# gprs_i2c.net
KiCad netlist of a schematic drawn in EAGLE
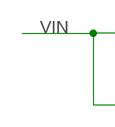
[diagram p0: schematic, sheet 1, part 1 of 2]
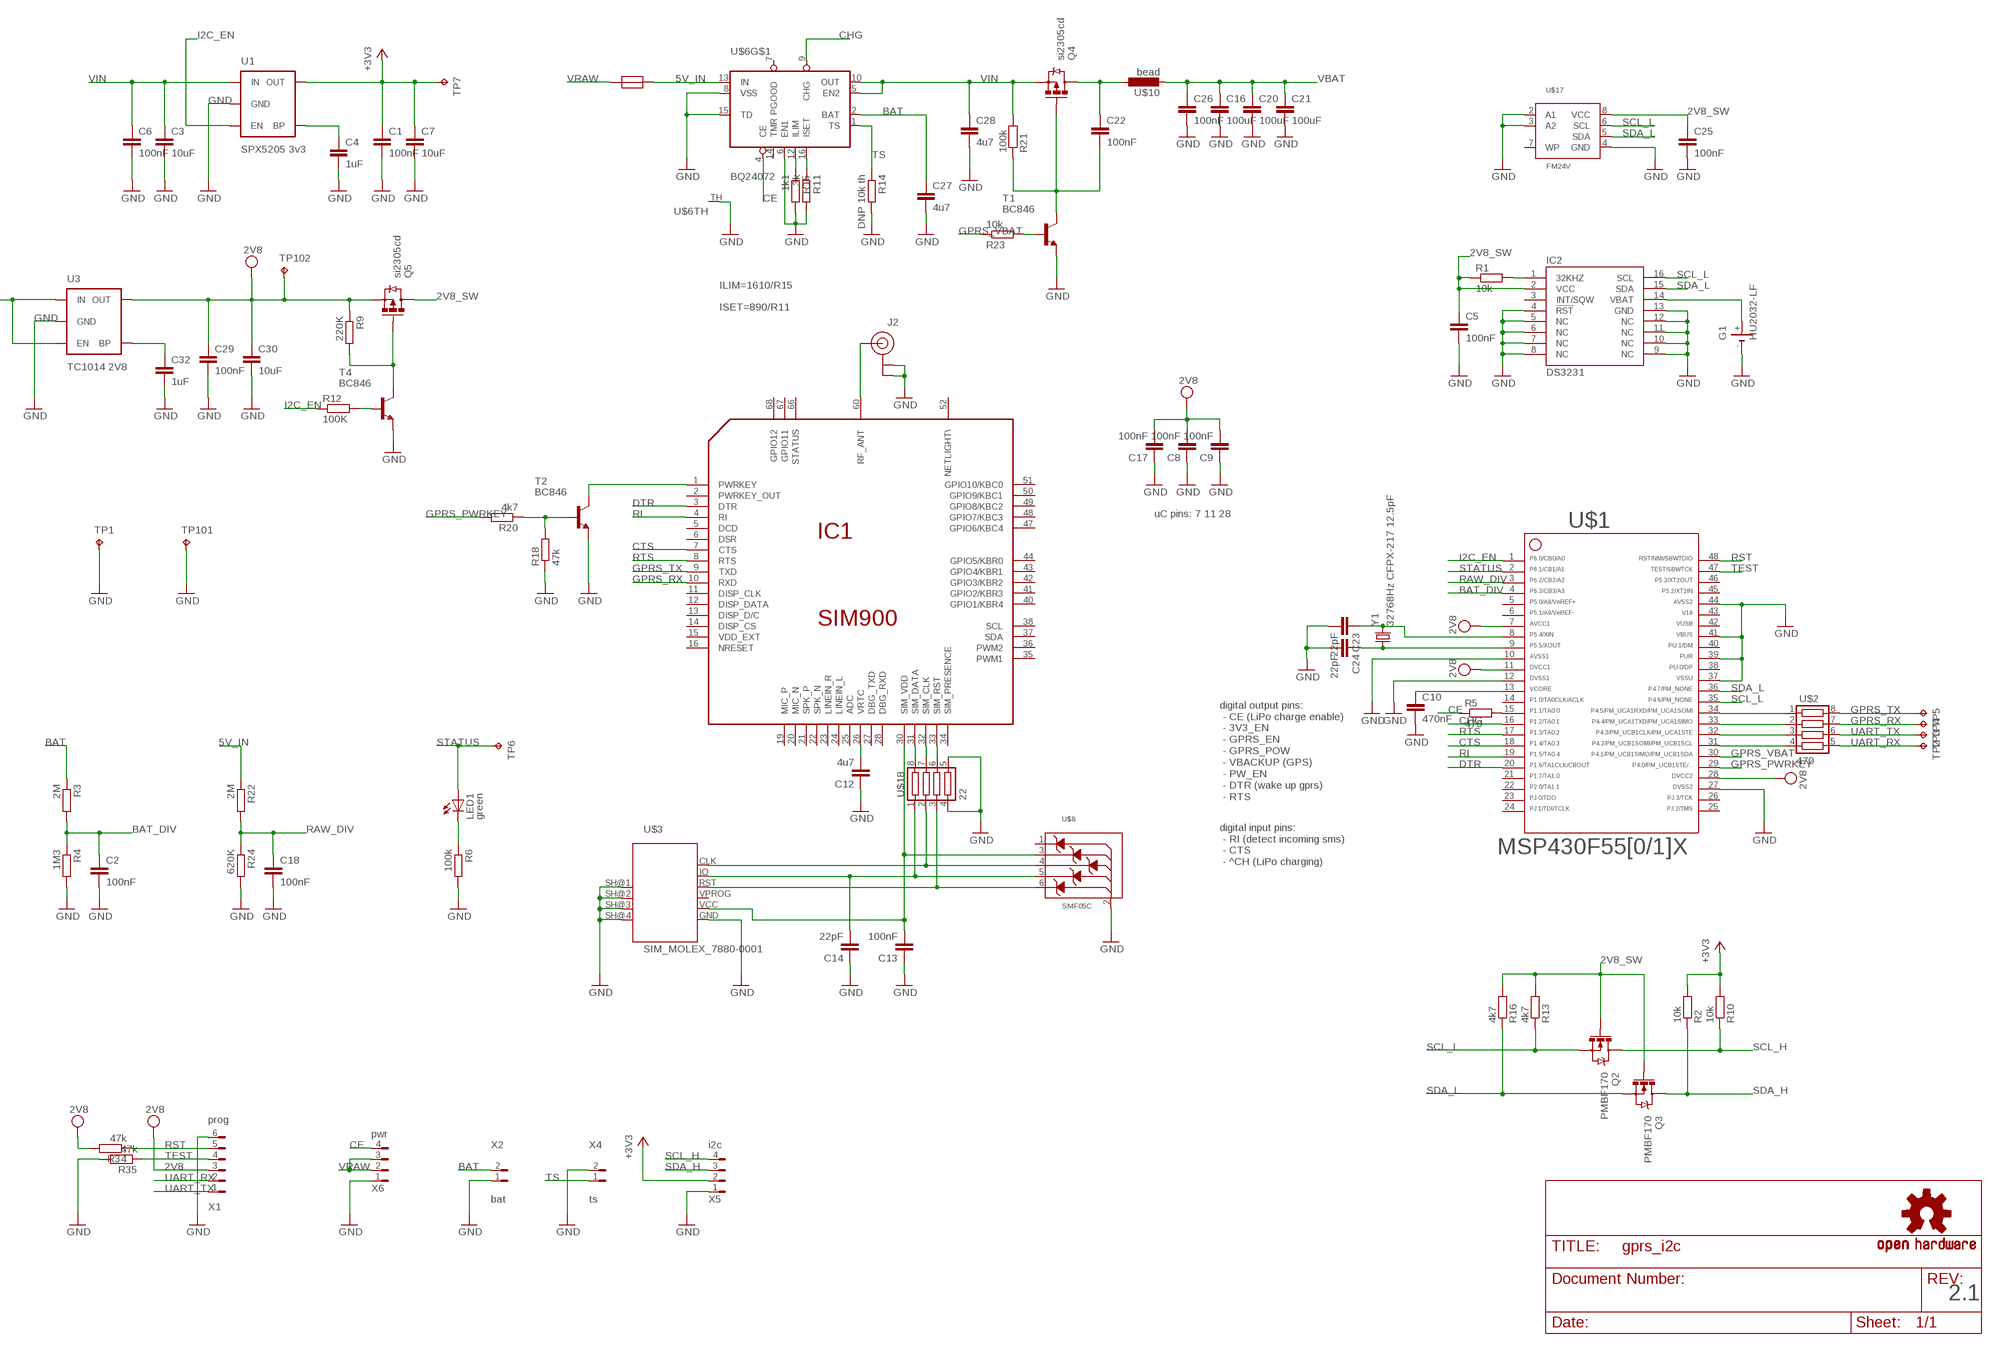
[diagram p1: schematic, sheet 1, part 2 of 2]

(export (version "E")
  (design (tool "Eeschema 10.0.6"))
  (components
    (comp (ref "C1")
      (value "100nF")
      (footprint "eagle-import:C0805")
      (libsource (lib "eagle-import") (part "C-EUC0805"))
    )
    (comp (ref "C2")
      (value "100nF")
      (footprint "eagle-import:C0805")
      (libsource (lib "eagle-import") (part "C-EUC0805"))
    )
    (comp (ref "C3")
      (value "10uF")
      (footprint "eagle-import:C0805")
      (libsource (lib "eagle-import") (part "C-EUC0805"))
    )
    (comp (ref "C4")
      (value "1uF")
      (footprint "eagle-import:C0805")
      (libsource (lib "eagle-import") (part "C-EUC0805"))
    )
    (comp (ref "C5")
      (value "100nF")
      (footprint "eagle-import:C0805")
      (libsource (lib "eagle-import") (part "C-EUC0805"))
    )
    (comp (ref "C6")
      (value "100nF")
      (footprint "eagle-import:C0805")
      (libsource (lib "eagle-import") (part "C-EUC0805"))
    )
    (comp (ref "C7")
      (value "10uF")
      (footprint "eagle-import:C1206")
      (libsource (lib "eagle-import") (part "C-EUC1206"))
    )
    (comp (ref "C8")
      (value "100nF")
      (footprint "eagle-import:C0805")
      (libsource (lib "eagle-import") (part "C-EUC0805"))
    )
    (comp (ref "C9")
      (value "100nF")
      (footprint "eagle-import:C0805")
      (libsource (lib "eagle-import") (part "C-EUC0805"))
    )
    (comp (ref "C10")
      (value "470nF")
      (footprint "eagle-import:C0805")
      (libsource (lib "eagle-import") (part "C-EUC0805"))
    )
    (comp (ref "C12")
      (value "4u7")
      (footprint "eagle-import:C0805")
      (libsource (lib "eagle-import") (part "C-EUC0805"))
    )
    (comp (ref "C13")
      (value "100nF")
      (footprint "eagle-import:C0805")
      (libsource (lib "eagle-import") (part "C-EUC0805"))
    )
    (comp (ref "C14")
      (value "22pF")
      (footprint "eagle-import:C0805")
      (libsource (lib "eagle-import") (part "C-EUC0805"))
    )
    (comp (ref "C16")
      (value "100uF")
      (footprint "eagle-import:C1206")
      (libsource (lib "eagle-import") (part "C-EUC1206"))
    )
    (comp (ref "C17")
      (value "100nF")
      (footprint "eagle-import:C0805")
      (libsource (lib "eagle-import") (part "C-EUC0805"))
    )
    (comp (ref "C18")
      (value "100nF")
      (footprint "eagle-import:C0805")
      (libsource (lib "eagle-import") (part "C-EUC0805"))
    )
    (comp (ref "C20")
      (value "100uF")
      (footprint "eagle-import:C1206")
      (libsource (lib "eagle-import") (part "C-EUC1206"))
    )
    (comp (ref "C21")
      (value "100uF")
      (footprint "eagle-import:C1206")
      (libsource (lib "eagle-import") (part "C-EUC1206"))
    )
    (comp (ref "C22")
      (value "100nF")
      (footprint "eagle-import:C0805")
      (libsource (lib "eagle-import") (part "C-EUC0805"))
    )
    (comp (ref "C23")
      (value "22pF")
      (footprint "eagle-import:C0805")
      (libsource (lib "eagle-import") (part "C-EUC0805"))
    )
    (comp (ref "C24")
      (value "22pF")
      (footprint "eagle-import:C0805")
      (libsource (lib "eagle-import") (part "C-EUC0805"))
    )
    (comp (ref "C25")
      (value "100nF")
      (footprint "eagle-import:C0805")
      (libsource (lib "eagle-import") (part "C-EUC0805"))
    )
    (comp (ref "C26")
      (value "100nF")
      (footprint "eagle-import:C0805")
      (libsource (lib "eagle-import") (part "C-EUC0805"))
    )
    (comp (ref "C27")
      (value "4u7")
      (footprint "eagle-import:C1206")
      (libsource (lib "eagle-import") (part "C-EUC1206"))
    )
    (comp (ref "C28")
      (value "4u7")
      (footprint "eagle-import:C1206")
      (libsource (lib "eagle-import") (part "C-EUC1206"))
    )
    (comp (ref "C29")
      (value "100nF")
      (footprint "eagle-import:C0805")
      (libsource (lib "eagle-import") (part "C-EUC0805"))
    )
    (comp (ref "C30")
      (value "10uF")
      (footprint "eagle-import:C1206")
      (libsource (lib "eagle-import") (part "C-EUC1206"))
    )
    (comp (ref "C32")
      (value "1uF")
      (footprint "eagle-import:C0805")
      (libsource (lib "eagle-import") (part "C-EUC0805"))
    )
    (comp (ref "G1")
      (value "HU2032-LF")
      (footprint "eagle-import:HU2032-LF")
      (libsource (lib "eagle-import") (part "HU2032-LF"))
    )
    (comp (ref "IC1")
      (value "SIM900")
      (footprint "eagle-import:SIM900")
      (libsource (lib "eagle-import") (part "SIM900"))
    )
    (comp (ref "IC2")
      (value "DS3231")
      (footprint "eagle-import:SO-16")
      (libsource (lib "eagle-import") (part "DS3231"))
    )
    (comp (ref "J2")
      (value "U.FL")
      (footprint "eagle-import:U.FL")
      (libsource (lib "eagle-import") (part "U.FL"))
    )
    (comp (ref "LED1")
      (value "green")
      (footprint "eagle-import:CHIPLED_0805")
      (libsource (lib "eagle-import") (part "LEDCHIPLED_0805"))
    )
    (comp (ref "Q2")
      (value "PMBF170")
      (footprint "eagle-import:SOT23-3")
      (libsource (lib "eagle-import") (part "MOSFET-NCHANNEL_SOT23-3"))
    )
    (comp (ref "Q3")
      (value "PMBF170")
      (footprint "eagle-import:SOT23-3")
      (libsource (lib "eagle-import") (part "MOSFET-NCHANNEL_SOT23-3"))
    )
    (comp (ref "Q4")
      (value "si2305cd")
      (footprint "eagle-import:SOT23-3_POWER@1")
      (libsource (lib "eagle-import") (part "MOSFET-PCHANNELSMD_POWER"))
    )
    (comp (ref "Q5")
      (value "si2305cd")
      (footprint "eagle-import:SOT23-3_POWER@1")
      (libsource (lib "eagle-import") (part "MOSFET-PCHANNELSMD_POWER"))
    )
    (comp (ref "R1")
      (value "10k")
      (footprint "eagle-import:R0805W")
      (libsource (lib "eagle-import") (part "R-EU_R0805W"))
    )
    (comp (ref "R2")
      (value "10k")
      (footprint "eagle-import:R0805W")
      (libsource (lib "eagle-import") (part "R-EU_R0805W"))
    )
    (comp (ref "R3")
      (value "2M")
      (footprint "eagle-import:R0805W")
      (libsource (lib "eagle-import") (part "R-EU_R0805W"))
    )
    (comp (ref "R4")
      (value "1M3")
      (footprint "eagle-import:R0805W")
      (libsource (lib "eagle-import") (part "R-EU_R0805W"))
    )
    (comp (ref "R5")
      (value "470")
      (footprint "eagle-import:R0805W")
      (libsource (lib "eagle-import") (part "R-EU_R0805W"))
    )
    (comp (ref "R6")
      (value "100k")
      (footprint "eagle-import:R0805W")
      (libsource (lib "eagle-import") (part "R-EU_R0805W"))
    )
    (comp (ref "R9")
      (value "220K")
      (footprint "eagle-import:R0805W")
      (libsource (lib "eagle-import") (part "R-EU_R0805W"))
    )
    (comp (ref "R10")
      (value "10k")
      (footprint "eagle-import:R0805W")
      (libsource (lib "eagle-import") (part "R-EU_R0805W"))
    )
    (comp (ref "R11")
      (value "3k")
      (footprint "eagle-import:R0805W")
      (libsource (lib "eagle-import") (part "R-EU_R0805W"))
    )
    (comp (ref "R12")
      (value "100K")
      (footprint "eagle-import:R0805W")
      (libsource (lib "eagle-import") (part "R-EU_R0805W"))
    )
    (comp (ref "R13")
      (value "4k7")
      (footprint "eagle-import:R0805W")
      (libsource (lib "eagle-import") (part "R-EU_R0805W"))
    )
    (comp (ref "R14")
      (value "DNP 10k th")
      (footprint "eagle-import:R0805W")
      (libsource (lib "eagle-import") (part "R-EU_R0805W"))
    )
    (comp (ref "R15")
      (value "1k1")
      (footprint "eagle-import:R0805W")
      (libsource (lib "eagle-import") (part "R-EU_R0805W"))
    )
    (comp (ref "R16")
      (value "4k7")
      (footprint "eagle-import:R0805W")
      (libsource (lib "eagle-import") (part "R-EU_R0805W"))
    )
    (comp (ref "R18")
      (value "47k")
      (footprint "eagle-import:R0805W")
      (libsource (lib "eagle-import") (part "R-EU_R0805W"))
    )
    (comp (ref "R20")
      (value "4k7")
      (footprint "eagle-import:R0805W")
      (libsource (lib "eagle-import") (part "R-EU_R0805W"))
    )
    (comp (ref "R21")
      (value "100k")
      (footprint "eagle-import:R0805W")
      (libsource (lib "eagle-import") (part "R-EU_R0805W"))
    )
    (comp (ref "R22")
      (value "2M")
      (footprint "eagle-import:R0805W")
      (libsource (lib "eagle-import") (part "R-EU_R0805W"))
    )
    (comp (ref "R23")
      (value "10k")
      (footprint "eagle-import:R0805W")
      (libsource (lib "eagle-import") (part "R-EU_R0805W"))
    )
    (comp (ref "R24")
      (value "620K")
      (footprint "eagle-import:R0805W")
      (libsource (lib "eagle-import") (part "R-EU_R0805W"))
    )
    (comp (ref "R34")
      (value "47k")
      (footprint "eagle-import:R0805W")
      (libsource (lib "eagle-import") (part "R-EU_R0805W"))
    )
    (comp (ref "R35")
      (value "47k")
      (footprint "eagle-import:R0805W")
      (libsource (lib "eagle-import") (part "R-EU_R0805W"))
    )
    (comp (ref "T1")
      (value "BC846")
      (footprint "eagle-import:SOT23")
      (libsource (lib "eagle-import") (part "BC846"))
    )
    (comp (ref "T2")
      (value "BC846")
      (footprint "eagle-import:SOT23")
      (libsource (lib "eagle-import") (part "BC846"))
    )
    (comp (ref "T4")
      (value "BC846")
      (footprint "eagle-import:SOT23")
      (libsource (lib "eagle-import") (part "BC846"))
    )
    (comp (ref "TP1")
      (value "TPTP12R")
      (footprint "eagle-import:TP12R")
      (libsource (lib "eagle-import") (part "TPTP12R"))
    )
    (comp (ref "TP2")
      (value "TPTP12R")
      (footprint "eagle-import:TP12R")
      (libsource (lib "eagle-import") (part "TPTP12R"))
    )
    (comp (ref "TP3")
      (value "TPTP12R")
      (footprint "eagle-import:TP12R")
      (libsource (lib "eagle-import") (part "TPTP12R"))
    )
    (comp (ref "TP4")
      (value "TPTP12R")
      (footprint "eagle-import:TP12R")
      (libsource (lib "eagle-import") (part "TPTP12R"))
    )
    (comp (ref "TP5")
      (value "TPTP12R")
      (footprint "eagle-import:TP12R")
      (libsource (lib "eagle-import") (part "TPTP12R"))
    )
    (comp (ref "TP6")
      (value "TPTP12R")
      (footprint "eagle-import:TP12R")
      (libsource (lib "eagle-import") (part "TPTP12R"))
    )
    (comp (ref "TP7")
      (value "TPTP12R")
      (footprint "eagle-import:TP12R")
      (libsource (lib "eagle-import") (part "TPTP12R"))
    )
    (comp (ref "TP101")
      (value "TPTP12R")
      (footprint "eagle-import:TP12R")
      (libsource (lib "eagle-import") (part "TPTP12R"))
    )
    (comp (ref "TP102")
      (value "TPTP12R")
      (footprint "eagle-import:TP12R")
      (libsource (lib "eagle-import") (part "TPTP12R"))
    )
    (comp (ref "U$1")
      (value "MSP430F5510")
      (footprint "eagle-import:PT48")
      (libsource (lib "eagle-import") (part "F55[0/1]X---PT48"))
    )
    (comp (ref "U$2")
      (value "470")
      (footprint "eagle-import:YC164")
      (libsource (lib "eagle-import") (part "RES_ARR"))
    )
    (comp (ref "U$3")
      (value "SIM_MOLEX_7880-0001")
      (footprint "eagle-import:MOLEX_7880-0001")
      (libsource (lib "eagle-import") (part "SIM_MOLEX_7880-0001"))
    )
    (comp (ref "U$5")
      (value "RESETTABLE_0805")
      (footprint "eagle-import:0805W")
      (libsource (lib "eagle-import") (part "RESETTABLE_0805"))
    )
    (comp (ref "U$6")
      (value "BQ24072")
      (footprint "eagle-import:S-PVQFN-N16")
      (libsource (lib "eagle-import") (part "BQ24072"))
    )
    (comp (ref "U$7")
      (value "OSHW-LOGOM")
      (footprint "eagle-import:OSHW-LOGO-M")
      (libsource (lib "eagle-import") (part "OSHW-LOGOM"))
    )
    (comp (ref "U$8")
      (value "SMF05C")
      (footprint "eagle-import:SC-88")
      (libsource (lib "eagle-import") (part "SMF05C"))
    )
    (comp (ref "U$10")
      (value "bead")
      (footprint "eagle-import:L0805W")
      (libsource (lib "eagle-import") (part "INDUCTOR"))
    )
    (comp (ref "U$17")
      (value "FM24V")
      (footprint "eagle-import:SO-08")
      (libsource (lib "eagle-import") (part "FM24V"))
    )
    (comp (ref "U$18")
      (value "22")
      (footprint "eagle-import:YC164")
      (libsource (lib "eagle-import") (part "RES_ARR"))
    )
    (comp (ref "U1")
      (value "SPX5205 3v3")
      (footprint "eagle-import:SOT23-5")
      (libsource (lib "eagle-import") (part "V_REG_LDOSMD"))
    )
    (comp (ref "U3")
      (value "TC1014 2V8")
      (footprint "eagle-import:SOT23-5")
      (libsource (lib "eagle-import") (part "V_REG_LDOSMD"))
    )
    (comp (ref "X1")
      (value "prog")
      (footprint "eagle-import:0530470610")
      (libsource (lib "eagle-import") (part "MOLEX_6VERTICAL"))
    )
    (comp (ref "X2")
      (value "bat")
      (footprint "eagle-import:0530480210")
      (libsource (lib "eagle-import") (part "MOLEX_2HORIZONTAL"))
    )
    (comp (ref "X4")
      (value "ts")
      (footprint "eagle-import:0530480210")
      (libsource (lib "eagle-import") (part "MOLEX_2HORIZONTAL"))
    )
    (comp (ref "X5")
      (value "i2c")
      (footprint "eagle-import:0530480401")
      (libsource (lib "eagle-import") (part "MOLEX_4HORIZONTAL"))
    )
    (comp (ref "X6")
      (value "pwr")
      (footprint "eagle-import:0530480401")
      (libsource (lib "eagle-import") (part "MOLEX_4HORIZONTAL"))
    )
    (comp (ref "Y1")
      (value "32768Hz CFPX-217 12.5pF")
      (footprint "eagle-import:CRYSTAL-SMD-3.2X1.5")
      (libsource (lib "eagle-import") (part "CRYSTAL3.2X1.5"))
    )
  )
  (nets
    (net (code "1") (name "+3V3") (class "Default")
      (node (ref "C1") (pin "1") (pinfunction "1_1") (pintype "passive"))
      (node (ref "C7") (pin "1") (pinfunction "1_1") (pintype "passive"))
      (node (ref "R10") (pin "2") (pinfunction "2_2") (pintype "passive"))
      (node (ref "R2") (pin "2") (pinfunction "2_2") (pintype "passive"))
      (node (ref "TP7") (pin "TP") (pinfunction "TP_TP") (pintype "input"))
      (node (ref "U1") (pin "5") (pinfunction "OUT_5") (pintype "passive"))
      (node (ref "X5") (pin "2") (pinfunction "3_2") (pintype "passive"))
    )
    (net (code "2") (name "/2V8_SW") (class "Default")
      (node (ref "C25") (pin "1") (pinfunction "1_1") (pintype "passive"))
      (node (ref "C5") (pin "1") (pinfunction "1_1") (pintype "passive"))
      (node (ref "IC2") (pin "2") (pinfunction "VCC_2") (pintype "power_in"))
      (node (ref "Q2") (pin "1") (pinfunction "G_1") (pintype "passive"))
      (node (ref "Q3") (pin "1") (pinfunction "G_1") (pintype "passive"))
      (node (ref "Q5") (pin "3") (pinfunction "D_3") (pintype "passive"))
      (node (ref "R1") (pin "1") (pinfunction "1_1") (pintype "passive"))
      (node (ref "R13") (pin "2") (pinfunction "2_2") (pintype "passive"))
      (node (ref "R16") (pin "2") (pinfunction "2_2") (pintype "passive"))
      (node (ref "U$17") (pin "8") (pinfunction "VCC_8") (pintype "bidirectional"))
    )
    (net (code "3") (name "/5V_IN") (class "Default")
      (node (ref "R22") (pin "1") (pinfunction "1_1") (pintype "passive"))
      (node (ref "U$5") (pin "2") (pinfunction "P$2_2") (pintype "bidirectional"))
      (node (ref "U$6") (pin "13") (pinfunction "IN_13") (pintype "input"))
    )
    (net (code "4") (name "/42") (class "Default")
      (node (ref "U$1") (pin "42") (pinfunction "42_42") (pintype "power_in"))
    )
    (net (code "5") (name "/43") (class "Default")
      (node (ref "U$1") (pin "43") (pinfunction "43_43") (pintype "power_in"))
    )
    (net (code "6") (name "/46") (class "Default")
      (node (ref "U$1") (pin "46") (pinfunction "46_46") (pintype "power_in"))
    )
    (net (code "7") (name "/BAT") (class "Default")
      (node (ref "C27") (pin "1") (pinfunction "1_1") (pintype "passive"))
      (node (ref "R3") (pin "1") (pinfunction "1_1") (pintype "passive"))
      (node (ref "U$6") (pin "2") (pinfunction "BAT_2") (pintype "input"))
      (node (ref "X2") (pin "2") (pinfunction "1_2") (pintype "passive"))
    )
    (net (code "8") (name "/BAT_DIV") (class "Default")
      (node (ref "C2") (pin "1") (pinfunction "1_1") (pintype "passive"))
      (node (ref "R3") (pin "2") (pinfunction "2_2") (pintype "passive"))
      (node (ref "R4") (pin "1") (pinfunction "1_1") (pintype "passive"))
      (node (ref "U$1") (pin "4") (pinfunction "4_4") (pintype "bidirectional"))
    )
    (net (code "9") (name "/CE") (class "Default")
      (node (ref "R5") (pin "1") (pinfunction "1_1") (pintype "passive"))
      (node (ref "U$6") (pin "4") (pinfunction "CE_4") (pintype "bidirectional"))
      (node (ref "X6") (pin "4") (pinfunction "1_4") (pintype "passive"))
    )
    (net (code "10") (name "/CHG") (class "Default")
      (node (ref "U$1") (pin "16") (pinfunction "16_16") (pintype "bidirectional"))
      (node (ref "U$6") (pin "9") (pinfunction "CHG_9") (pintype "bidirectional"))
    )
    (net (code "11") (name "/CTS") (class "Default")
      (node (ref "IC1") (pin "7") (pinfunction "CTS_7") (pintype "bidirectional"))
      (node (ref "U$1") (pin "18") (pinfunction "18_18") (pintype "bidirectional"))
    )
    (net (code "12") (name "/DTR") (class "Default")
      (node (ref "IC1") (pin "3") (pinfunction "DTR_3") (pintype "bidirectional"))
      (node (ref "U$1") (pin "20") (pinfunction "20_20") (pintype "bidirectional"))
    )
    (net (code "13") (name "/GPRS_PWRKEY") (class "Default")
      (node (ref "R20") (pin "2") (pinfunction "2_2") (pintype "passive"))
      (node (ref "U$1") (pin "29") (pinfunction "29_29") (pintype "bidirectional"))
    )
    (net (code "14") (name "/GPRS_RX") (class "Default")
      (node (ref "IC1") (pin "10") (pinfunction "RXD_10") (pintype "bidirectional"))
      (node (ref "TP4") (pin "TP") (pinfunction "TP_TP") (pintype "input"))
      (node (ref "U$2") (pin "7") (pinfunction "7_7") (pintype "passive"))
    )
    (net (code "15") (name "/GPRS_TX") (class "Default")
      (node (ref "IC1") (pin "9") (pinfunction "TXD_9") (pintype "bidirectional"))
      (node (ref "TP5") (pin "TP") (pinfunction "TP_TP") (pintype "input"))
      (node (ref "U$2") (pin "8") (pinfunction "8_8") (pintype "passive"))
    )
    (net (code "16") (name "/GPRS_VBAT") (class "Default")
      (node (ref "R23") (pin "1") (pinfunction "1_1") (pintype "passive"))
      (node (ref "U$1") (pin "30") (pinfunction "30_30") (pintype "bidirectional"))
    )
    (net (code "17") (name "/I2C_EN") (class "Default")
      (node (ref "R12") (pin "1") (pinfunction "1_1") (pintype "passive"))
      (node (ref "U$1") (pin "1") (pinfunction "1_1") (pintype "bidirectional"))
      (node (ref "U1") (pin "3") (pinfunction "EN_3") (pintype "input"))
    )
    (net (code "18") (name "/RAW_DIV") (class "Default")
      (node (ref "C18") (pin "1") (pinfunction "1_1") (pintype "passive"))
      (node (ref "R22") (pin "2") (pinfunction "2_2") (pintype "passive"))
      (node (ref "R24") (pin "1") (pinfunction "1_1") (pintype "passive"))
      (node (ref "U$1") (pin "3") (pinfunction "3_3") (pintype "bidirectional"))
    )
    (net (code "19") (name "/RI") (class "Default")
      (node (ref "IC1") (pin "4") (pinfunction "RI_4") (pintype "bidirectional"))
      (node (ref "U$1") (pin "19") (pinfunction "19_19") (pintype "bidirectional"))
    )
    (net (code "20") (name "/RST") (class "Default")
      (node (ref "R34") (pin "1") (pinfunction "1_1") (pintype "passive"))
      (node (ref "U$1") (pin "48") (pinfunction "48_48") (pintype "bidirectional"))
      (node (ref "X1") (pin "5") (pinfunction "5_5") (pintype "passive"))
    )
    (net (code "21") (name "/RTS") (class "Default")
      (node (ref "IC1") (pin "8") (pinfunction "RTS_8") (pintype "bidirectional"))
      (node (ref "U$1") (pin "17") (pinfunction "17_17") (pintype "bidirectional"))
    )
    (net (code "22") (name "/SCL_H") (class "Default")
      (node (ref "Q2") (pin "3") (pinfunction "D_3") (pintype "passive"))
      (node (ref "R10") (pin "1") (pinfunction "1_1") (pintype "passive"))
      (node (ref "X5") (pin "4") (pinfunction "1_4") (pintype "passive"))
    )
    (net (code "23") (name "/SCL_L") (class "Default")
      (node (ref "IC2") (pin "16") (pinfunction "SCL_16") (pintype "bidirectional"))
      (node (ref "Q2") (pin "2") (pinfunction "S_2") (pintype "passive"))
      (node (ref "R13") (pin "1") (pinfunction "1_1") (pintype "passive"))
      (node (ref "U$1") (pin "35") (pinfunction "35_35") (pintype "bidirectional"))
      (node (ref "U$17") (pin "6") (pinfunction "SCL_6") (pintype "bidirectional"))
    )
    (net (code "24") (name "/SDA_H") (class "Default")
      (node (ref "Q3") (pin "3") (pinfunction "D_3") (pintype "passive"))
      (node (ref "R2") (pin "1") (pinfunction "1_1") (pintype "passive"))
      (node (ref "X5") (pin "3") (pinfunction "2_3") (pintype "passive"))
    )
    (net (code "25") (name "/SDA_L") (class "Default")
      (node (ref "IC2") (pin "15") (pinfunction "SDA_15") (pintype "bidirectional"))
      (node (ref "Q3") (pin "2") (pinfunction "S_2") (pintype "passive"))
      (node (ref "R16") (pin "1") (pinfunction "1_1") (pintype "passive"))
      (node (ref "U$1") (pin "36") (pinfunction "36_36") (pintype "bidirectional"))
      (node (ref "U$17") (pin "5") (pinfunction "SDA_5") (pintype "bidirectional"))
    )
    (net (code "26") (name "/STATUS") (class "Default")
      (node (ref "LED1") (pin "A") (pinfunction "A_A") (pintype "passive"))
      (node (ref "TP6") (pin "TP") (pinfunction "TP_TP") (pintype "input"))
      (node (ref "U$1") (pin "2") (pinfunction "2_2") (pintype "bidirectional"))
    )
    (net (code "27") (name "/TEST") (class "Default")
      (node (ref "R35") (pin "1") (pinfunction "1_1") (pintype "passive"))
      (node (ref "U$1") (pin "47") (pinfunction "47_47") (pintype "input"))
      (node (ref "X1") (pin "4") (pinfunction "4_4") (pintype "passive"))
    )
    (net (code "28") (name "/TS") (class "Default")
      (node (ref "R14") (pin "1") (pinfunction "1_1") (pintype "passive"))
      (node (ref "U$6") (pin "1") (pinfunction "TS_1") (pintype "input"))
      (node (ref "X4") (pin "1") (pinfunction "2_1") (pintype "passive"))
    )
    (net (code "29") (name "/UART_RX") (class "Default")
      (node (ref "TP2") (pin "TP") (pinfunction "TP_TP") (pintype "input"))
      (node (ref "U$2") (pin "5") (pinfunction "5_5") (pintype "passive"))
      (node (ref "X1") (pin "2") (pinfunction "2_2") (pintype "passive"))
    )
    (net (code "30") (name "/UART_TX") (class "Default")
      (node (ref "TP3") (pin "TP") (pinfunction "TP_TP") (pintype "input"))
      (node (ref "U$2") (pin "6") (pinfunction "6_6") (pintype "passive"))
      (node (ref "X1") (pin "1") (pinfunction "1_1") (pintype "passive"))
    )
    (net (code "31") (name "/VBAT") (class "Default")
      (node (ref "C16") (pin "1") (pinfunction "1_1") (pintype "passive"))
      (node (ref "C20") (pin "1") (pinfunction "1_1") (pintype "passive"))
      (node (ref "C21") (pin "1") (pinfunction "1_1") (pintype "passive"))
      (node (ref "C26") (pin "1") (pinfunction "1_1") (pintype "passive"))
      (node (ref "U$10") (pin "2") (pinfunction "2_2") (pintype "passive"))
    )
    (net (code "32") (name "/VIN") (class "Default")
      (node (ref "C28") (pin "1") (pinfunction "1_1") (pintype "passive"))
      (node (ref "C3") (pin "1") (pinfunction "1_1") (pintype "passive"))
      (node (ref "C6") (pin "1") (pinfunction "1_1") (pintype "passive"))
      (node (ref "Q4") (pin "2") (pinfunction "S_2") (pintype "passive"))
      (node (ref "R21") (pin "2") (pinfunction "2_2") (pintype "passive"))
      (node (ref "U$6") (pin "10") (pinfunction "OUT_10") (pintype "output"))
      (node (ref "U$6") (pin "5") (pinfunction "EN2_5") (pintype "input"))
      (node (ref "U1") (pin "1") (pinfunction "IN_1") (pintype "input"))
      (node (ref "U3") (pin "1") (pinfunction "IN_1") (pintype "input"))
      (node (ref "U3") (pin "3") (pinfunction "EN_3") (pintype "input"))
    )
    (net (code "33") (name "/VRAW") (class "Default")
      (node (ref "U$5") (pin "1") (pinfunction "P$1_1") (pintype "bidirectional"))
      (node (ref "X6") (pin "2") (pinfunction "3_2") (pintype "passive"))
      (node (ref "X6") (pin "3") (pinfunction "2_3") (pintype "passive"))
    )
    (net (code "34") (name "2V8") (class "Default")
      (node (ref "C17") (pin "2") (pinfunction "2_2") (pintype "passive"))
      (node (ref "C29") (pin "1") (pinfunction "1_1") (pintype "passive"))
      (node (ref "C30") (pin "1") (pinfunction "1_1") (pintype "passive"))
      (node (ref "C8") (pin "2") (pinfunction "2_2") (pintype "passive"))
      (node (ref "C9") (pin "2") (pinfunction "2_2") (pintype "passive"))
      (node (ref "Q5") (pin "2") (pinfunction "S_2") (pintype "passive"))
      (node (ref "R34") (pin "2") (pinfunction "2_2") (pintype "passive"))
      (node (ref "R9") (pin "1") (pinfunction "1_1") (pintype "passive"))
      (node (ref "TP102") (pin "TP") (pinfunction "TP_TP") (pintype "input"))
      (node (ref "U$1") (pin "11") (pinfunction "11_11") (pintype "power_in"))
      (node (ref "U$1") (pin "28") (pinfunction "28_28") (pintype "power_in"))
      (node (ref "U$1") (pin "7") (pinfunction "7_7") (pintype "power_in"))
      (node (ref "U3") (pin "5") (pinfunction "OUT_5") (pintype "passive"))
      (node (ref "X1") (pin "3") (pinfunction "3_3") (pintype "passive"))
    )
    (net (code "35") (name "GND") (class "Default")
      (node (ref "C1") (pin "2") (pinfunction "2_2") (pintype "passive"))
      (node (ref "C10") (pin "2") (pinfunction "2_2") (pintype "passive"))
      (node (ref "C12") (pin "1") (pinfunction "1_1") (pintype "passive"))
      (node (ref "C13") (pin "1") (pinfunction "1_1") (pintype "passive"))
      (node (ref "C14") (pin "1") (pinfunction "1_1") (pintype "passive"))
      (node (ref "C16") (pin "2") (pinfunction "2_2") (pintype "passive"))
      (node (ref "C17") (pin "1") (pinfunction "1_1") (pintype "passive"))
      (node (ref "C18") (pin "2") (pinfunction "2_2") (pintype "passive"))
      (node (ref "C2") (pin "2") (pinfunction "2_2") (pintype "passive"))
      (node (ref "C20") (pin "2") (pinfunction "2_2") (pintype "passive"))
      (node (ref "C21") (pin "2") (pinfunction "2_2") (pintype "passive"))
      (node (ref "C23") (pin "2") (pinfunction "2_2") (pintype "passive"))
      (node (ref "C24") (pin "2") (pinfunction "2_2") (pintype "passive"))
      (node (ref "C25") (pin "2") (pinfunction "2_2") (pintype "passive"))
      (node (ref "C26") (pin "2") (pinfunction "2_2") (pintype "passive"))
      (node (ref "C27") (pin "2") (pinfunction "2_2") (pintype "passive"))
      (node (ref "C28") (pin "2") (pinfunction "2_2") (pintype "passive"))
      (node (ref "C29") (pin "2") (pinfunction "2_2") (pintype "passive"))
      (node (ref "C3") (pin "2") (pinfunction "2_2") (pintype "passive"))
      (node (ref "C30") (pin "2") (pinfunction "2_2") (pintype "passive"))
      (node (ref "C32") (pin "2") (pinfunction "2_2") (pintype "passive"))
      (node (ref "C4") (pin "2") (pinfunction "2_2") (pintype "passive"))
      (node (ref "C5") (pin "2") (pinfunction "2_2") (pintype "passive"))
      (node (ref "C6") (pin "2") (pinfunction "2_2") (pintype "passive"))
      (node (ref "C7") (pin "2") (pinfunction "2_2") (pintype "passive"))
      (node (ref "C8") (pin "1") (pinfunction "1_1") (pintype "passive"))
      (node (ref "C9") (pin "1") (pinfunction "1_1") (pintype "passive"))
      (node (ref "G1") (pin "-") (pinfunction "-_-") (pintype "passive"))
      (node (ref "IC2") (pin "10") (pinfunction "NC_10") (pintype "bidirectional"))
      (node (ref "IC2") (pin "11") (pinfunction "NC_11") (pintype "bidirectional"))
      (node (ref "IC2") (pin "12") (pinfunction "NC_12") (pintype "bidirectional"))
      (node (ref "IC2") (pin "13") (pinfunction "GND_13") (pintype "power_in"))
      (node (ref "IC2") (pin "4") (pinfunction "~{RST}_4") (pintype "bidirectional"))
      (node (ref "IC2") (pin "5") (pinfunction "NC_5") (pintype "bidirectional"))
      (node (ref "IC2") (pin "6") (pinfunction "NC_6") (pintype "bidirectional"))
      (node (ref "IC2") (pin "7") (pinfunction "NC_7") (pintype "bidirectional"))
      (node (ref "IC2") (pin "8") (pinfunction "NC_8") (pintype "bidirectional"))
      (node (ref "IC2") (pin "9") (pinfunction "NC_9") (pintype "bidirectional"))
      (node (ref "J2") (pin "P$1") (pinfunction "GND_P$1") (pintype "bidirectional"))
      (node (ref "J2") (pin "P$2") (pinfunction "GND_P$2") (pintype "bidirectional"))
      (node (ref "R11") (pin "2") (pinfunction "2_2") (pintype "passive"))
      (node (ref "R14") (pin "2") (pinfunction "2_2") (pintype "passive"))
      (node (ref "R15") (pin "2") (pinfunction "2_2") (pintype "passive"))
      (node (ref "R18") (pin "1") (pinfunction "1_1") (pintype "passive"))
      (node (ref "R24") (pin "2") (pinfunction "2_2") (pintype "passive"))
      (node (ref "R35") (pin "2") (pinfunction "2_2") (pintype "passive"))
      (node (ref "R4") (pin "2") (pinfunction "2_2") (pintype "passive"))
      (node (ref "R6") (pin "2") (pinfunction "2_2") (pintype "passive"))
      (node (ref "T1") (pin "2") (pinfunction "E_2") (pintype "passive"))
      (node (ref "T2") (pin "2") (pinfunction "E_2") (pintype "passive"))
      (node (ref "T4") (pin "2") (pinfunction "E_2") (pintype "passive"))
      (node (ref "TP1") (pin "TP") (pinfunction "TP_TP") (pintype "input"))
      (node (ref "TP101") (pin "TP") (pinfunction "TP_TP") (pintype "input"))
      (node (ref "U$1") (pin "10") (pinfunction "10_10") (pintype "power_in"))
      (node (ref "U$1") (pin "12") (pinfunction "12_12") (pintype "power_in"))
      (node (ref "U$1") (pin "27") (pinfunction "27_27") (pintype "power_in"))
      (node (ref "U$1") (pin "37") (pinfunction "37_37") (pintype "power_in"))
      (node (ref "U$1") (pin "39") (pinfunction "39_39") (pintype "bidirectional"))
      (node (ref "U$1") (pin "41") (pinfunction "41_41") (pintype "power_in"))
      (node (ref "U$1") (pin "44") (pinfunction "44_44") (pintype "power_in"))
      (node (ref "U$17") (pin "2") (pinfunction "A1_2") (pintype "bidirectional"))
      (node (ref "U$17") (pin "3") (pinfunction "A2_3") (pintype "bidirectional"))
      (node (ref "U$17") (pin "4") (pinfunction "GND_4") (pintype "bidirectional"))
      (node (ref "U$18") (pin "4") (pinfunction "4_4") (pintype "passive"))
      (node (ref "U$18") (pin "5") (pinfunction "5_5") (pintype "passive"))
      (node (ref "U$3") (pin "GND") (pinfunction "GND_GND") (pintype "bidirectional"))
      (node (ref "U$3") (pin "SH@1") (pinfunction "SH_SH@1") (pintype "bidirectional"))
      (node (ref "U$3") (pin "SH@2") (pinfunction "SH_SH@2") (pintype "bidirectional"))
      (node (ref "U$3") (pin "SH@3") (pinfunction "SH_SH@3") (pintype "bidirectional"))
      (node (ref "U$3") (pin "SH@4") (pinfunction "SH_SH@4") (pintype "bidirectional"))
      (node (ref "U$6") (pin "15") (pinfunction "TD_15") (pintype "bidirectional"))
      (node (ref "U$6") (pin "6") (pinfunction "EN1_6") (pintype "bidirectional"))
      (node (ref "U$6") (pin "8") (pinfunction "VSS_8") (pintype "power_in"))
      (node (ref "U$6") (pin "TH") (pinfunction "TH_TH") (pintype "passive"))
      (node (ref "U$8") (pin "2") (pinfunction "ANODE_2") (pintype "passive"))
      (node (ref "U1") (pin "2") (pinfunction "GND_2") (pintype "input"))
      (node (ref "U3") (pin "2") (pinfunction "GND_2") (pintype "input"))
      (node (ref "X1") (pin "6") (pinfunction "6_6") (pintype "passive"))
      (node (ref "X2") (pin "1") (pinfunction "2_1") (pintype "passive"))
      (node (ref "X4") (pin "2") (pinfunction "1_2") (pintype "passive"))
      (node (ref "X5") (pin "1") (pinfunction "4_1") (pintype "passive"))
      (node (ref "X6") (pin "1") (pinfunction "4_1") (pintype "passive"))
    )
    (net (code "36") (name "Net-(C10-Pad1)") (class "Default")
      (node (ref "C10") (pin "1") (pinfunction "1_1") (pintype "passive"))
      (node (ref "U$1") (pin "13") (pinfunction "13_13") (pintype "power_in"))
    )
    (net (code "37") (name "Net-(IC1A-PWRKEY)") (class "Default")
      (node (ref "IC1") (pin "1") (pinfunction "PWRKEY_1") (pintype "bidirectional"))
      (node (ref "T2") (pin "3") (pinfunction "C_3") (pintype "passive"))
    )
    (net (code "38") (name "Net-(IC1A-RF_ANT)") (class "Default")
      (node (ref "IC1") (pin "60") (pinfunction "RF_ANT_60") (pintype "bidirectional"))
      (node (ref "J2") (pin "P$3") (pinfunction "SIGNAL_P$3") (pintype "bidirectional"))
    )
    (net (code "39") (name "Net-(IC1A-SIM_CLK)") (class "Default")
      (node (ref "IC1") (pin "32") (pinfunction "SIM_CLK_32") (pintype "bidirectional"))
      (node (ref "U$18") (pin "7") (pinfunction "7_7") (pintype "passive"))
    )
    (net (code "40") (name "Net-(IC1A-SIM_DATA)") (class "Default")
      (node (ref "IC1") (pin "31") (pinfunction "SIM_DATA_31") (pintype "bidirectional"))
      (node (ref "U$18") (pin "8") (pinfunction "8_8") (pintype "passive"))
    )
    (net (code "41") (name "Net-(IC1A-SIM_RST)") (class "Default")
      (node (ref "IC1") (pin "33") (pinfunction "SIM_RST_33") (pintype "bidirectional"))
      (node (ref "U$18") (pin "6") (pinfunction "6_6") (pintype "passive"))
    )
    (net (code "42") (name "Net-(IC1A-SIM_VDD)") (class "Default")
      (node (ref "C13") (pin "2") (pinfunction "2_2") (pintype "passive"))
      (node (ref "IC1") (pin "30") (pinfunction "SIM_VDD_30") (pintype "bidirectional"))
      (node (ref "U$3") (pin "VCC") (pinfunction "VCC_VCC") (pintype "bidirectional"))
      (node (ref "U$8") (pin "3") (pinfunction "CATODE2_3") (pintype "passive"))
    )
    (net (code "43") (name "Net-(IC1A-VRTC)") (class "Default")
      (node (ref "C12") (pin "2") (pinfunction "2_2") (pintype "passive"))
      (node (ref "IC1") (pin "26") (pinfunction "VRTC_26") (pintype "bidirectional"))
    )
    (net (code "44") (name "Net-(IC2-32KHZ)") (class "Default")
      (node (ref "IC2") (pin "1") (pinfunction "32KHZ_1") (pintype "bidirectional"))
      (node (ref "R1") (pin "2") (pinfunction "2_2") (pintype "passive"))
    )
    (net (code "45") (name "Net-(IC2-VBAT)") (class "Default")
      (node (ref "G1") (pin "+") (pinfunction "+_+") (pintype "passive"))
      (node (ref "IC2") (pin "14") (pinfunction "VBAT_14") (pintype "bidirectional"))
    )
    (net (code "46") (name "Net-(LED1-PadC)") (class "Default")
      (node (ref "LED1") (pin "C") (pinfunction "C_C") (pintype "passive"))
      (node (ref "R6") (pin "1") (pinfunction "1_1") (pintype "passive"))
    )
    (net (code "47") (name "Net-(Q4-D)") (class "Default")
      (node (ref "C22") (pin "1") (pinfunction "1_1") (pintype "passive"))
      (node (ref "Q4") (pin "3") (pinfunction "D_3") (pintype "passive"))
      (node (ref "U$10") (pin "1") (pinfunction "1_1") (pintype "passive"))
    )
    (net (code "48") (name "Net-(Q4-G)") (class "Default")
      (node (ref "C22") (pin "2") (pinfunction "2_2") (pintype "passive"))
      (node (ref "Q4") (pin "1") (pinfunction "G_1") (pintype "passive"))
      (node (ref "R21") (pin "1") (pinfunction "1_1") (pintype "passive"))
      (node (ref "T1") (pin "3") (pinfunction "C_3") (pintype "passive"))
    )
    (net (code "49") (name "Net-(Q5-G)") (class "Default")
      (node (ref "Q5") (pin "1") (pinfunction "G_1") (pintype "passive"))
      (node (ref "R9") (pin "2") (pinfunction "2_2") (pintype "passive"))
      (node (ref "T4") (pin "3") (pinfunction "C_3") (pintype "passive"))
    )
    (net (code "50") (name "Net-(R5-Pad2)") (class "Default")
      (node (ref "R5") (pin "2") (pinfunction "2_2") (pintype "passive"))
      (node (ref "U$1") (pin "15") (pinfunction "15_15") (pintype "bidirectional"))
    )
    (net (code "51") (name "Net-(T1-B)") (class "Default")
      (node (ref "R23") (pin "2") (pinfunction "2_2") (pintype "passive"))
      (node (ref "T1") (pin "1") (pinfunction "B_1") (pintype "passive"))
    )
    (net (code "52") (name "Net-(T2-B)") (class "Default")
      (node (ref "R18") (pin "2") (pinfunction "2_2") (pintype "passive"))
      (node (ref "R20") (pin "1") (pinfunction "1_1") (pintype "passive"))
      (node (ref "T2") (pin "1") (pinfunction "B_1") (pintype "passive"))
    )
    (net (code "53") (name "Net-(T4-B)") (class "Default")
      (node (ref "R12") (pin "2") (pinfunction "2_2") (pintype "passive"))
      (node (ref "T4") (pin "1") (pinfunction "B_1") (pintype "passive"))
    )
    (net (code "54") (name "Net-(U$1-Pad31)") (class "Default")
      (node (ref "U$1") (pin "31") (pinfunction "31_31") (pintype "bidirectional"))
      (node (ref "U$2") (pin "4") (pinfunction "4_4") (pintype "passive"))
    )
    (net (code "55") (name "Net-(U$1-Pad32)") (class "Default")
      (node (ref "U$1") (pin "32") (pinfunction "32_32") (pintype "bidirectional"))
      (node (ref "U$2") (pin "3") (pinfunction "3_3") (pintype "passive"))
    )
    (net (code "56") (name "Net-(U$1-Pad33)") (class "Default")
      (node (ref "U$1") (pin "33") (pinfunction "33_33") (pintype "bidirectional"))
      (node (ref "U$2") (pin "2") (pinfunction "2_2") (pintype "passive"))
    )
    (net (code "57") (name "Net-(U$1-Pad34)") (class "Default")
      (node (ref "U$1") (pin "34") (pinfunction "34_34") (pintype "bidirectional"))
      (node (ref "U$2") (pin "1") (pinfunction "1_1") (pintype "passive"))
    )
    (net (code "58") (name "Net-(U$6A-ILIM)") (class "Default")
      (node (ref "R15") (pin "1") (pinfunction "1_1") (pintype "passive"))
      (node (ref "U$6") (pin "12") (pinfunction "ILIM_12") (pintype "bidirectional"))
    )
    (net (code "59") (name "Net-(U$6A-ISET)") (class "Default")
      (node (ref "R11") (pin "1") (pinfunction "1_1") (pintype "passive"))
      (node (ref "U$6") (pin "16") (pinfunction "ISET_16") (pintype "input"))
    )
    (net (code "60") (name "Net-(U$8-CATODE3)") (class "Default")
      (node (ref "U$18") (pin "2") (pinfunction "2_2") (pintype "passive"))
      (node (ref "U$3") (pin "CLK") (pinfunction "CLK_CLK") (pintype "bidirectional"))
      (node (ref "U$8") (pin "4") (pinfunction "CATODE3_4") (pintype "passive"))
    )
    (net (code "61") (name "Net-(U$8-CATODE4)") (class "Default")
      (node (ref "C14") (pin "2") (pinfunction "2_2") (pintype "passive"))
      (node (ref "U$18") (pin "1") (pinfunction "1_1") (pintype "passive"))
      (node (ref "U$3") (pin "IO") (pinfunction "IO_IO") (pintype "bidirectional"))
      (node (ref "U$8") (pin "5") (pinfunction "CATODE4_5") (pintype "passive"))
    )
    (net (code "62") (name "Net-(U$8-CATODE5)") (class "Default")
      (node (ref "U$18") (pin "3") (pinfunction "3_3") (pintype "passive"))
      (node (ref "U$3") (pin "RST") (pinfunction "RST_RST") (pintype "bidirectional"))
      (node (ref "U$8") (pin "6") (pinfunction "CATODE5_6") (pintype "passive"))
    )
    (net (code "63") (name "Net-(U1-BP)") (class "Default")
      (node (ref "C4") (pin "1") (pinfunction "1_1") (pintype "passive"))
      (node (ref "U1") (pin "4") (pinfunction "BP_4") (pintype "input"))
    )
    (net (code "64") (name "Net-(U3-BP)") (class "Default")
      (node (ref "C32") (pin "1") (pinfunction "1_1") (pintype "passive"))
      (node (ref "U3") (pin "4") (pinfunction "BP_4") (pintype "input"))
    )
    (net (code "65") (name "Net-(Y1-1)") (class "Default")
      (node (ref "C24") (pin "1") (pinfunction "1_1") (pintype "passive"))
      (node (ref "U$1") (pin "9") (pinfunction "9_9") (pintype "bidirectional"))
      (node (ref "Y1") (pin "P$1") (pinfunction "1_P$1") (pintype "passive"))
    )
    (net (code "66") (name "Net-(Y1-2)") (class "Default")
      (node (ref "C23") (pin "1") (pinfunction "1_1") (pintype "passive"))
      (node (ref "U$1") (pin "8") (pinfunction "8_8") (pintype "bidirectional"))
      (node (ref "Y1") (pin "P$2") (pinfunction "2_P$2") (pintype "passive"))
    )
    (net (code "67") (name "unconnected-(G1-+-Pad+@1)") (class "Default")
      (node (ref "G1") (pin "+@1") (pinfunction "+_+@1") (pintype "passive"))
    )
    (net (code "68") (name "unconnected-(IC1A-ADC-Pad25)") (class "Default")
      (node (ref "IC1") (pin "25") (pinfunction "ADC_25") (pintype "bidirectional"))
    )
    (net (code "69") (name "unconnected-(IC1A-DBG_RXD-Pad28)") (class "Default")
      (node (ref "IC1") (pin "28") (pinfunction "DBG_RXD_28") (pintype "bidirectional"))
    )
    (net (code "70") (name "unconnected-(IC1A-DBG_TXD-Pad27)") (class "Default")
      (node (ref "IC1") (pin "27") (pinfunction "DBG_TXD_27") (pintype "bidirectional"))
    )
    (net (code "71") (name "unconnected-(IC1A-DCD-Pad5)") (class "Default")
      (node (ref "IC1") (pin "5") (pinfunction "DCD_5") (pintype "bidirectional"))
    )
    (net (code "72") (name "unconnected-(IC1A-DISP_CLK-Pad11)") (class "Default")
      (node (ref "IC1") (pin "11") (pinfunction "DISP_CLK_11") (pintype "bidirectional"))
    )
    (net (code "73") (name "unconnected-(IC1A-DISP_CS-Pad14)") (class "Default")
      (node (ref "IC1") (pin "14") (pinfunction "DISP_CS_14") (pintype "bidirectional"))
    )
    (net (code "74") (name "unconnected-(IC1A-DISP_DATA-Pad12)") (class "Default")
      (node (ref "IC1") (pin "12") (pinfunction "DISP_DATA_12") (pintype "bidirectional"))
    )
    (net (code "75") (name "unconnected-(IC1A-DISP_D{slash}C-Pad13)") (class "Default")
      (node (ref "IC1") (pin "13") (pinfunction "DISP_D/C_13") (pintype "bidirectional"))
    )
    (net (code "76") (name "unconnected-(IC1A-DSR-Pad6)") (class "Default")
      (node (ref "IC1") (pin "6") (pinfunction "DSR_6") (pintype "bidirectional"))
    )
    (net (code "77") (name "unconnected-(IC1A-GPIO1{slash}KBR4-Pad40)") (class "Default")
      (node (ref "IC1") (pin "40") (pinfunction "GPIO1/KBR4_40") (pintype "bidirectional"))
    )
    (net (code "78") (name "unconnected-(IC1A-GPIO2{slash}KBR3-Pad41)") (class "Default")
      (node (ref "IC1") (pin "41") (pinfunction "GPIO2/KBR3_41") (pintype "bidirectional"))
    )
    (net (code "79") (name "unconnected-(IC1A-GPIO3{slash}KBR2-Pad42)") (class "Default")
      (node (ref "IC1") (pin "42") (pinfunction "GPIO3/KBR2_42") (pintype "bidirectional"))
    )
    (net (code "80") (name "unconnected-(IC1A-GPIO4{slash}KBR1-Pad43)") (class "Default")
      (node (ref "IC1") (pin "43") (pinfunction "GPIO4/KBR1_43") (pintype "bidirectional"))
    )
    (net (code "81") (name "unconnected-(IC1A-GPIO5{slash}KBR0-Pad44)") (class "Default")
      (node (ref "IC1") (pin "44") (pinfunction "GPIO5/KBR0_44") (pintype "bidirectional"))
    )
    (net (code "82") (name "unconnected-(IC1A-GPIO6{slash}KBC4-Pad47)") (class "Default")
      (node (ref "IC1") (pin "47") (pinfunction "GPIO6/KBC4_47") (pintype "bidirectional"))
    )
    (net (code "83") (name "unconnected-(IC1A-GPIO7{slash}KBC3-Pad48)") (class "Default")
      (node (ref "IC1") (pin "48") (pinfunction "GPIO7/KBC3_48") (pintype "bidirectional"))
    )
    (net (code "84") (name "unconnected-(IC1A-GPIO8{slash}KBC2-Pad49)") (class "Default")
      (node (ref "IC1") (pin "49") (pinfunction "GPIO8/KBC2_49") (pintype "bidirectional"))
    )
    (net (code "85") (name "unconnected-(IC1A-GPIO9{slash}KBC1-Pad50)") (class "Default")
      (node (ref "IC1") (pin "50") (pinfunction "GPIO9/KBC1_50") (pintype "bidirectional"))
    )
    (net (code "86") (name "unconnected-(IC1A-GPIO10{slash}KBC0-Pad51)") (class "Default")
      (node (ref "IC1") (pin "51") (pinfunction "GPIO10/KBC0_51") (pintype "bidirectional"))
    )
    (net (code "87") (name "unconnected-(IC1A-GPIO11-Pad67)") (class "Default")
      (node (ref "IC1") (pin "67") (pinfunction "GPIO11_67") (pintype "bidirectional"))
    )
    (net (code "88") (name "unconnected-(IC1A-GPIO12-Pad68)") (class "Default")
      (node (ref "IC1") (pin "68") (pinfunction "GPIO12_68") (pintype "bidirectional"))
    )
    (net (code "89") (name "unconnected-(IC1A-LINEIN_L-Pad24)") (class "Default")
      (node (ref "IC1") (pin "24") (pinfunction "LINEIN_L_24") (pintype "bidirectional"))
    )
    (net (code "90") (name "unconnected-(IC1A-LINEIN_R-Pad23)") (class "Default")
      (node (ref "IC1") (pin "23") (pinfunction "LINEIN_R_23") (pintype "bidirectional"))
    )
    (net (code "91") (name "unconnected-(IC1A-MIC_N-Pad20)") (class "Default")
      (node (ref "IC1") (pin "20") (pinfunction "MIC_N_20") (pintype "bidirectional"))
    )
    (net (code "92") (name "unconnected-(IC1A-MIC_P-Pad19)") (class "Default")
      (node (ref "IC1") (pin "19") (pinfunction "MIC_P_19") (pintype "bidirectional"))
    )
    (net (code "93") (name "unconnected-(IC1A-NETLIGHT\\-Pad52)") (class "Default")
      (node (ref "IC1") (pin "52") (pinfunction "NETLIGHT\\_52") (pintype "bidirectional"))
    )
    (net (code "94") (name "unconnected-(IC1A-NRESET-Pad16)") (class "Default")
      (node (ref "IC1") (pin "16") (pinfunction "NRESET_16") (pintype "bidirectional"))
    )
    (net (code "95") (name "unconnected-(IC1A-PWM1-Pad35)") (class "Default")
      (node (ref "IC1") (pin "35") (pinfunction "PWM1_35") (pintype "bidirectional"))
    )
    (net (code "96") (name "unconnected-(IC1A-PWM2-Pad36)") (class "Default")
      (node (ref "IC1") (pin "36") (pinfunction "PWM2_36") (pintype "bidirectional"))
    )
    (net (code "97") (name "unconnected-(IC1A-PWRKEY_OUT-Pad2)") (class "Default")
      (node (ref "IC1") (pin "2") (pinfunction "PWRKEY_OUT_2") (pintype "bidirectional"))
    )
    (net (code "98") (name "unconnected-(IC1A-SCL-Pad38)") (class "Default")
      (node (ref "IC1") (pin "38") (pinfunction "SCL_38") (pintype "bidirectional"))
    )
    (net (code "99") (name "unconnected-(IC1A-SDA-Pad37)") (class "Default")
      (node (ref "IC1") (pin "37") (pinfunction "SDA_37") (pintype "bidirectional"))
    )
    (net (code "100") (name "unconnected-(IC1A-SIM_PRESENCE-Pad34)") (class "Default")
      (node (ref "IC1") (pin "34") (pinfunction "SIM_PRESENCE_34") (pintype "bidirectional"))
    )
    (net (code "101") (name "unconnected-(IC1A-SPK_N-Pad22)") (class "Default")
      (node (ref "IC1") (pin "22") (pinfunction "SPK_N_22") (pintype "bidirectional"))
    )
    (net (code "102") (name "unconnected-(IC1A-SPK_P-Pad21)") (class "Default")
      (node (ref "IC1") (pin "21") (pinfunction "SPK_P_21") (pintype "bidirectional"))
    )
    (net (code "103") (name "unconnected-(IC1A-STATUS-Pad66)") (class "Default")
      (node (ref "IC1") (pin "66") (pinfunction "STATUS_66") (pintype "bidirectional"))
    )
    (net (code "104") (name "unconnected-(IC1A-VDD_EXT-Pad15)") (class "Default")
      (node (ref "IC1") (pin "15") (pinfunction "VDD_EXT_15") (pintype "bidirectional"))
    )
    (net (code "105") (name "unconnected-(IC2-INT{slash}SQW-Pad3)") (class "Default")
      (node (ref "IC2") (pin "3") (pinfunction "INT/SQW_3") (pintype "bidirectional"))
    )
    (net (code "106") (name "unconnected-(U$1-Pad5)") (class "Default")
      (node (ref "U$1") (pin "5") (pinfunction "5_5") (pintype "bidirectional"))
    )
    (net (code "107") (name "unconnected-(U$1-Pad6)") (class "Default")
      (node (ref "U$1") (pin "6") (pinfunction "6_6") (pintype "bidirectional"))
    )
    (net (code "108") (name "unconnected-(U$1-Pad14)") (class "Default")
      (node (ref "U$1") (pin "14") (pinfunction "14_14") (pintype "bidirectional"))
    )
    (net (code "109") (name "unconnected-(U$1-Pad21)") (class "Default")
      (node (ref "U$1") (pin "21") (pinfunction "21_21") (pintype "bidirectional"))
    )
    (net (code "110") (name "unconnected-(U$1-Pad22)") (class "Default")
      (node (ref "U$1") (pin "22") (pinfunction "22_22") (pintype "bidirectional"))
    )
    (net (code "111") (name "unconnected-(U$1-Pad23)") (class "Default")
      (node (ref "U$1") (pin "23") (pinfunction "23_23") (pintype "bidirectional"))
    )
    (net (code "112") (name "unconnected-(U$1-Pad24)") (class "Default")
      (node (ref "U$1") (pin "24") (pinfunction "24_24") (pintype "bidirectional"))
    )
    (net (code "113") (name "unconnected-(U$1-Pad25)") (class "Default")
      (node (ref "U$1") (pin "25") (pinfunction "25_25") (pintype "bidirectional"))
    )
    (net (code "114") (name "unconnected-(U$1-Pad26)") (class "Default")
      (node (ref "U$1") (pin "26") (pinfunction "26_26") (pintype "bidirectional"))
    )
    (net (code "115") (name "unconnected-(U$1-Pad38)") (class "Default")
      (node (ref "U$1") (pin "38") (pinfunction "38_38") (pintype "bidirectional"))
    )
    (net (code "116") (name "unconnected-(U$1-Pad40)") (class "Default")
      (node (ref "U$1") (pin "40") (pinfunction "40_40") (pintype "bidirectional"))
    )
    (net (code "117") (name "unconnected-(U$1-Pad45)") (class "Default")
      (node (ref "U$1") (pin "45") (pinfunction "45_45") (pintype "bidirectional"))
    )
    (net (code "118") (name "unconnected-(U$3-PadVPROG)") (class "Default")
      (node (ref "U$3") (pin "VPROG") (pinfunction "VPROG_VPROG") (pintype "bidirectional"))
    )
    (net (code "119") (name "unconnected-(U$6A-PGOOD-Pad7)") (class "Default")
      (node (ref "U$6") (pin "7") (pinfunction "PGOOD_7") (pintype "bidirectional"))
    )
    (net (code "120") (name "unconnected-(U$6A-TMR-Pad14)") (class "Default")
      (node (ref "U$6") (pin "14") (pinfunction "TMR_14") (pintype "bidirectional"))
    )
    (net (code "121") (name "unconnected-(U$8-CATODE1-Pad1)") (class "Default")
      (node (ref "U$8") (pin "1") (pinfunction "CATODE1_1") (pintype "passive"))
    )
    (net (code "122") (name "unconnected-(U$17-WP-Pad7)") (class "Default")
      (node (ref "U$17") (pin "7") (pinfunction "WP_7") (pintype "bidirectional"))
    )
  )
)
